# Micro_USB_Port.net
KiCad netlist of a schematic drawn in Altium Designer
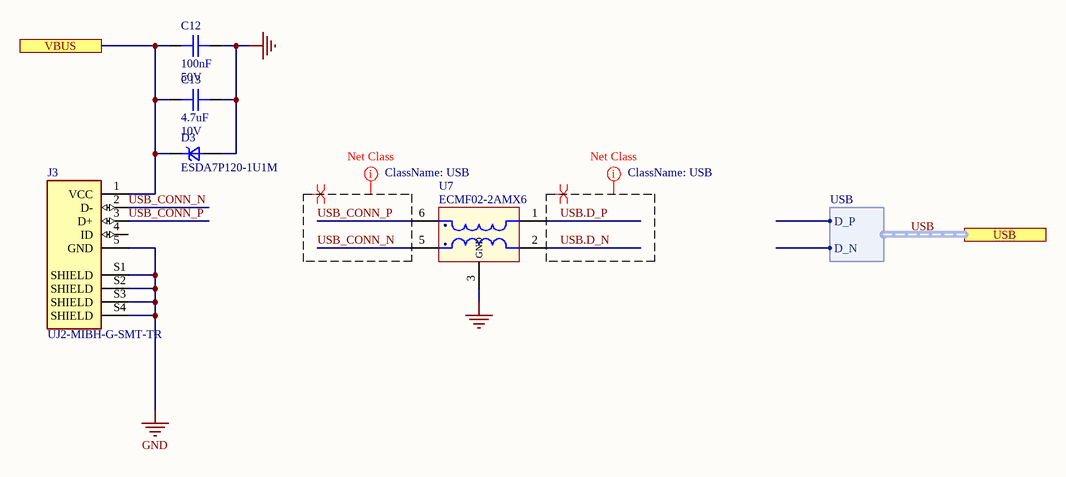
[diagram p0: Micro_USB_Port.SchDoc]

(export (version "E")
  (design (tool "Eeschema 10.0.6"))
  (components
    (comp (ref "C12")
      (value "~")
      (footprint "C0402")
      (description "0.1µF ±10% 50V Ceramic Capacitor X7R 0402 (1005 Metric)")
      (fields
        (field (name "MANUFACTURER") "TDK")
        (field (name "MANUFACTURER PART NUMBER") "CGA2B3X7R1H104K050BB")
        (field (name "CAPACITANCE") "100nF")
        (field (name "VOLTAGE") "50V")
      )
      (libsource (lib "capacitors_smd") (part "CAP CER 0.1UF 50V X7R 0402"))
    )
    (comp (ref "C13")
      (value "~")
      (footprint "0603C")
      (description "4.7µF ±10% 10V Ceramic Capacitor X5R 0603 (1608 Metric)")
      (fields
        (field (name "MANUFACTURER") "Yageo")
        (field (name "MANUFACTURER PART NUMBER") "CC0603KRX5R6BB475")
        (field (name "CAPACITANCE") "4.7uF")
        (field (name "VOLTAGE RATING") "10V")
      )
      (libsource (lib "capacitors_smd") (part "CAP CER 4.7UF 10V X5R 0603"))
    )
    (comp (ref "D3")
      (value "ESDA7P120-1U1M")
      (footprint "ST_QFN_1610")
      (description "11.5V Clamp 120A (8/20µs) Ipp Tvs Diode Surface Mount 1610")
      (fields (field (name "MANUFACTURER") "STMicroelectronics"))
      (libsource (lib "diodes_tvs") (part "TVS DIODE ESDA7P120-1U1M 5.5V 11.5V 1610"))
    )
    (comp (ref "J3")
      (value "UJ2-MIBH-G-SMT-TR")
      (footprint "CUI_UJ2-MIBH-G-SMT-TR")
      (description "Micro B, USB 2.0, 1.8 A, Right Angle, Surface Mount (SMT), USB Receptacle")
      (fields (field (name "MF") "CUI Devices"))
      (libsource (lib "UJ2-MIBH-G-SMT-TR-v2") (part "UJ2-MIBH-G-SMT-TR"))
    )
    (comp (ref "U7")
      (value "ECMF02-2AMX6")
      (footprint "QFN-6L")
      (description "2 Line Common Mode Choke Surface Mount  200mA DCR 2.5Ohm")
      (fields (field (name "MANUFACTURER") "STMicroelectronics"))
      (libsource (lib "diodes_tvs") (part "CMC 200MA 2LN SMD ESD"))
    )
  )
  (nets
    (net (code "2") (name "/USB.D_N") (class "Default")
      (node (ref "U7") (pin "2") (pinfunction "INP2_2") (pintype "passive"))
    )
    (net (code "3") (name "/USB.D_P") (class "Default")
      (node (ref "U7") (pin "1") (pinfunction "INP1_1") (pintype "passive"))
    )
    (net (code "4") (name "/USB_CONN_N") (class "Default")
      (node (ref "J3") (pin "2") (pinfunction "D-_2") (pintype "bidirectional"))
      (node (ref "U7") (pin "5") (pinfunction "OUT2_5") (pintype "passive"))
    )
    (net (code "5") (name "/USB_CONN_P") (class "Default")
      (node (ref "J3") (pin "3") (pinfunction "D+_3") (pintype "bidirectional"))
      (node (ref "U7") (pin "6") (pinfunction "OUT1_6") (pintype "passive"))
    )
    (net (code "7") (name "/VBUS") (class "Default")
      (node (ref "C12") (pin "2") (pinfunction "2_2") (pintype "passive"))
      (node (ref "C13") (pin "2") (pinfunction "2_2") (pintype "passive"))
      (node (ref "D3") (pin "1") (pinfunction "K_1") (pintype "passive"))
      (node (ref "J3") (pin "1") (pinfunction "VCC_1") (pintype "power_in"))
    )
    (net (code "8") (name "GND") (class "Default")
      (node (ref "C12") (pin "1") (pinfunction "1_1") (pintype "passive"))
      (node (ref "C13") (pin "1") (pinfunction "1_1") (pintype "passive"))
      (node (ref "D3") (pin "2") (pinfunction "A_2") (pintype "passive"))
      (node (ref "J3") (pin "5") (pinfunction "GND_5") (pintype "power_in"))
      (node (ref "J3") (pin "S1") (pinfunction "SHIELD_S1") (pintype "passive"))
      (node (ref "J3") (pin "S2") (pinfunction "SHIELD_S2") (pintype "passive"))
      (node (ref "J3") (pin "S3") (pinfunction "SHIELD_S3") (pintype "passive"))
      (node (ref "J3") (pin "S4") (pinfunction "SHIELD_S4") (pintype "passive"))
      (node (ref "U7") (pin "3") (pinfunction "GND_3") (pintype "power_in"))
    )
    (net (code "9") (name "unconnected-(J3-ID-Pad4)") (class "Default")
      (node (ref "J3") (pin "4") (pinfunction "ID_4") (pintype "bidirectional"))
    )
    (net (code "10") (name "unconnected-(U7-NC-Pad4)") (class "Default")
      (node (ref "U7") (pin "4") (pinfunction "NC_4") (pintype "passive"))
    )
  )
)
